# Bank_0_Bank_14.net
KiCad netlist of a schematic drawn in Altium Designer
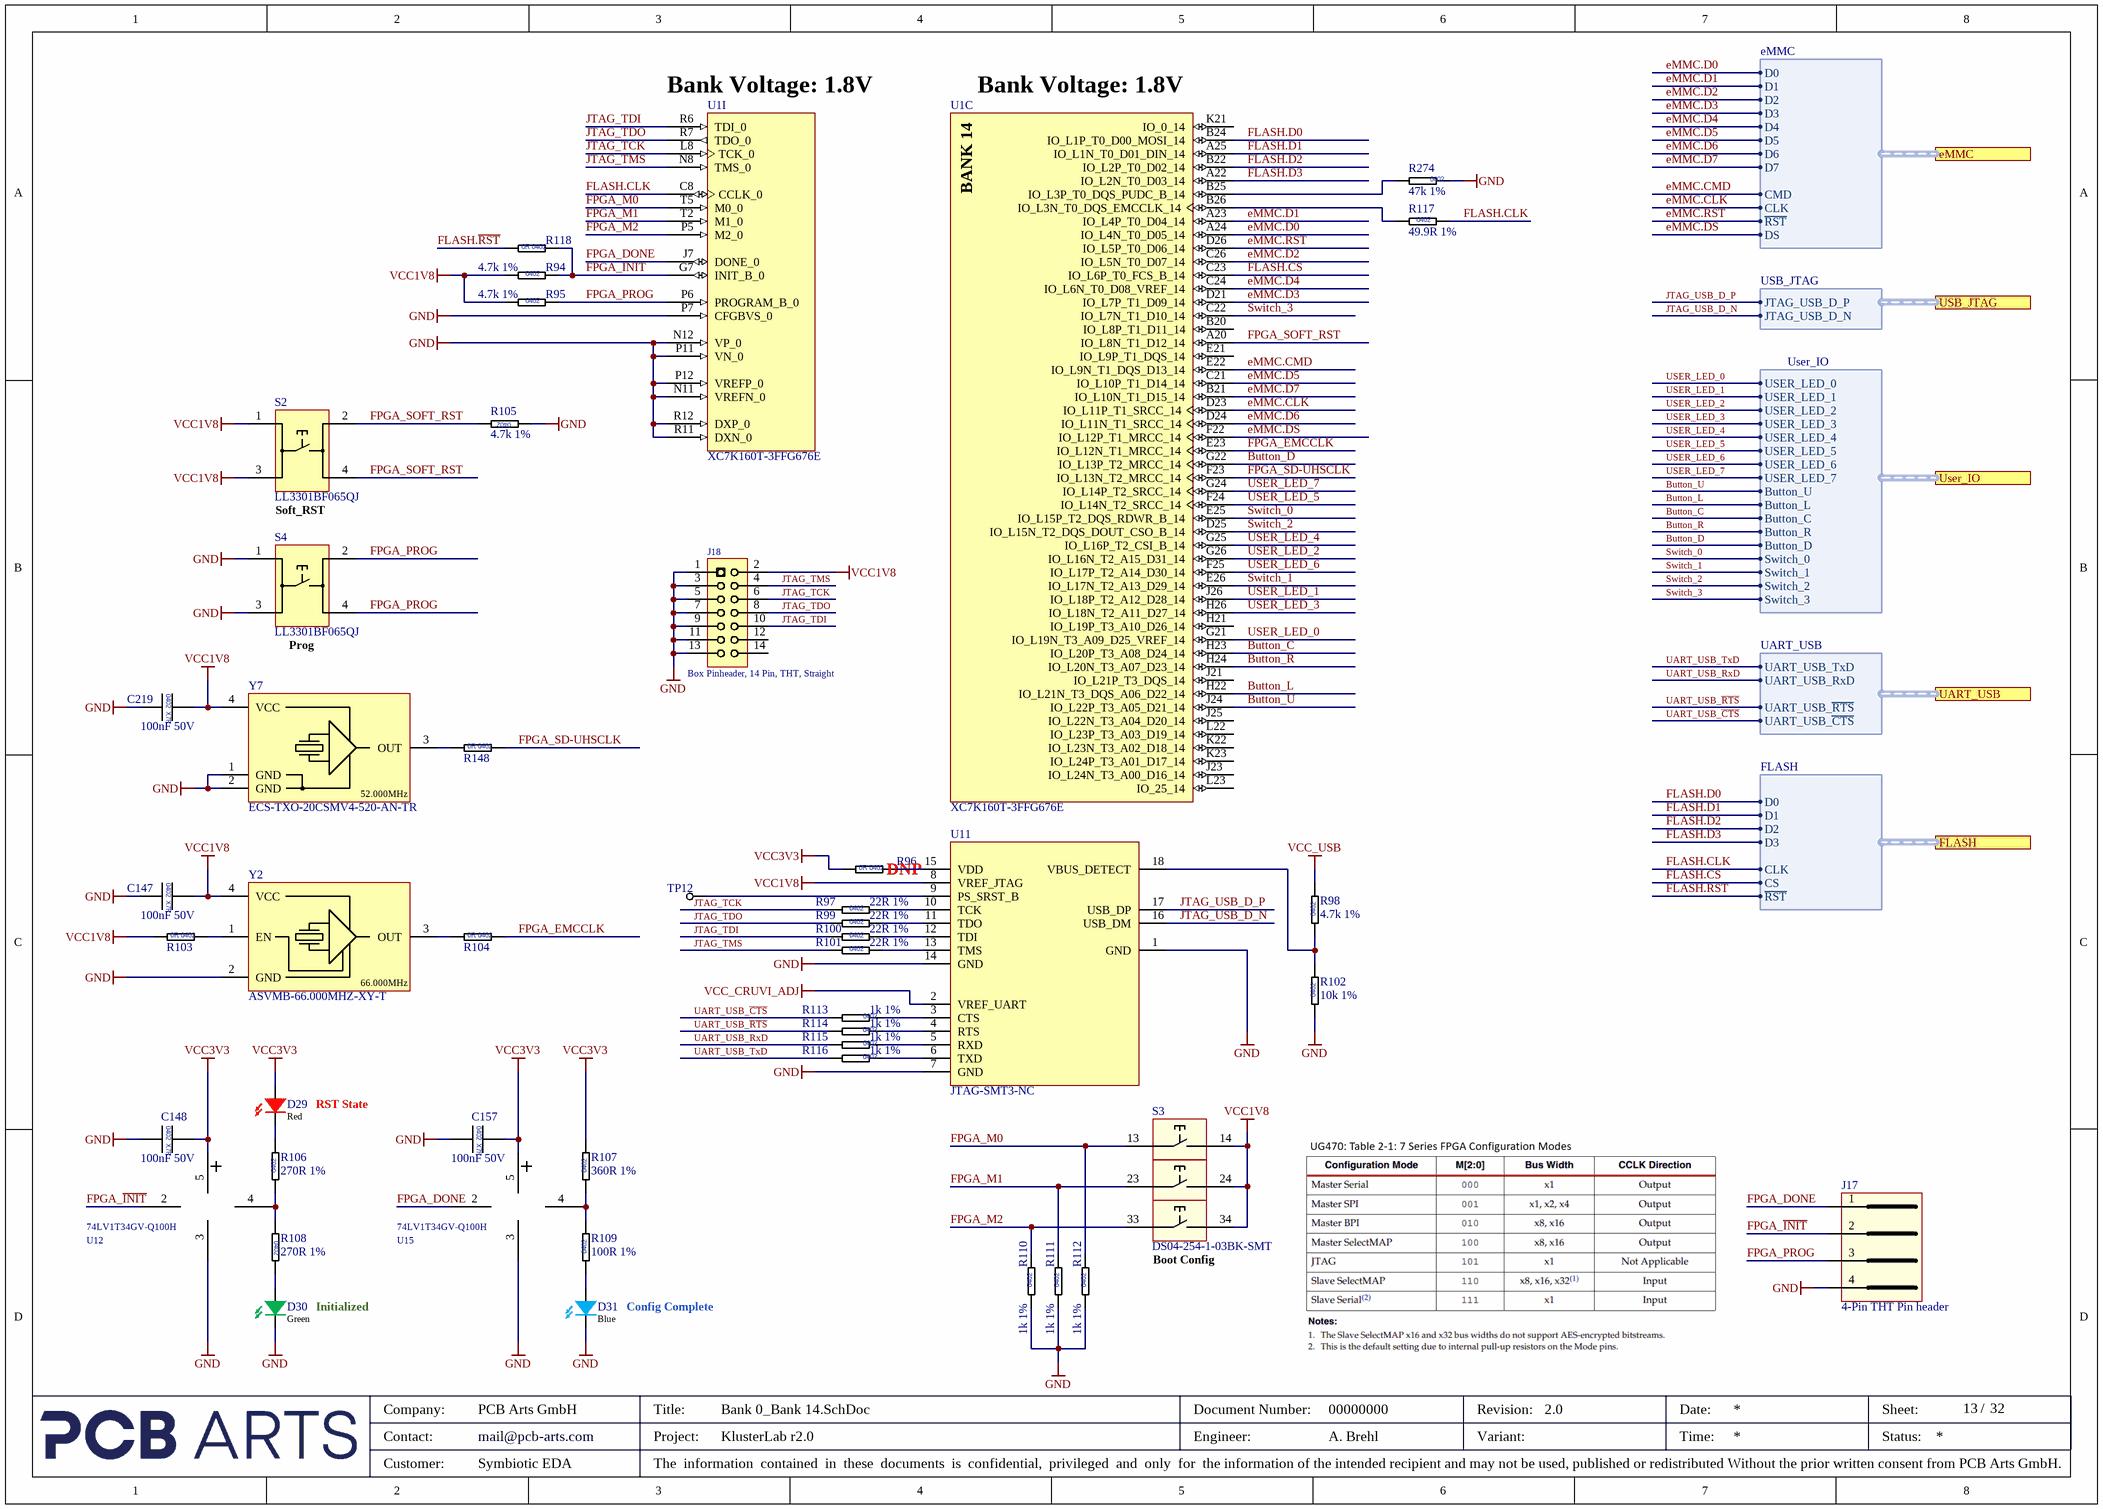
[diagram p0: Bank 0_Bank 14.SchDoc]

(export (version "E")
  (design (tool "Eeschema 10.0.6"))
  (components
    (comp (ref "C147")
      (value "100nF 50V")
      (footprint "Cap:CAP_0402_L")
      (description "Multilayer Ceramic Capacitors MLCC - SMD/SMT 0402 50VDC")
      (libsource (lib "Cap") (part "CAP_0402_100nF_50V"))
    )
    (comp (ref "C148")
      (value "100nF 50V")
      (footprint "Cap:CAP_0402_L")
      (description "Multilayer Ceramic Capacitors MLCC - SMD/SMT 0402 50VDC")
      (libsource (lib "Cap") (part "CAP_0402_100nF_50V"))
    )
    (comp (ref "C157")
      (value "100nF 50V")
      (footprint "Cap:CAP_0402_L")
      (description "Multilayer Ceramic Capacitors MLCC - SMD/SMT 0402 50VDC")
      (libsource (lib "Cap") (part "CAP_0402_100nF_50V"))
    )
    (comp (ref "C219")
      (value "100nF 50V")
      (footprint "Cap:CAP_0402_L")
      (description "Multilayer Ceramic Capacitors MLCC - SMD/SMT 0402 50VDC")
      (libsource (lib "Cap") (part "CAP_0402_100nF_50V"))
    )
    (comp (ref "D29")
      (value "LTST-S270KRKT")
      (footprint "Active:LED-0603 Sideview")
      (description "RED  0603 Light Emitting Diode")
      (fields (field (name "COLOR") "Red"))
      (libsource (lib "Active") (part "LED 0603 Red Sideview"))
    )
    (comp (ref "D30")
      (value "LTST-S270KGKT")
      (footprint "Active:LED-0603 Sideview")
      (description "GREEN  0603 Light Emitting Diode")
      (fields (field (name "COLOR") "Green"))
      (libsource (lib "Active") (part "LED 0603 Green Sideview"))
    )
    (comp (ref "D31")
      (value "LTST-S270TBKT")
      (footprint "Active:LED-0603 Sideview")
      (description "BLUE  0603 Light Emitting Diode")
      (fields (field (name "COLOR") "Blue"))
      (libsource (lib "Active") (part "LED 0603 Blue Sideview"))
    )
    (comp (ref "J17")
      (value "4-Pin THT Pin header")
      (footprint "Conn:61300411121")
      (description "WR-PHD 2.54mm 4Pin THT Header")
      (libsource (lib "Conn") (part "61300411121_WR-PHD 2.54mm 4Pin THT Header"))
    )
    (comp (ref "J18")
      (value "Box Pinheader, 14 Pin, THT, Straight")
      (footprint "Conn:87832-1420")
      (description "Box Pin header THT 2.00mm 14Pol Straight")
      (libsource (lib "Conn") (part "87832-1420_Box Pin header THT 2.00mm Box 14Pol Straight"))
    )
    (comp (ref "R94")
      (value "4.7k 1%")
      (footprint "Res:RES_0402_L")
      (description "Thick Film Resistors - SMD 4.7kOhm 1%")
      (libsource (lib "Res") (part "RES_0402_4.7k_1%"))
    )
    (comp (ref "R95")
      (value "4.7k 1%")
      (footprint "Res:RES_0402_L")
      (description "Thick Film Resistors - SMD 4.7kOhm 1%")
      (libsource (lib "Res") (part "RES_0402_4.7k_1%"))
    )
    (comp (ref "R96")
      (value "0R Jumper")
      (footprint "Res:RES_0402_L")
      (description "Thick Film Resistors - SMD 0Ohm")
      (libsource (lib "Res") (part "RES_0402_0R Jumper"))
    )
    (comp (ref "R97")
      (value "22R 1%")
      (footprint "Res:RES_0402_L")
      (description "Thick Film Resistors - SMD 22Ohm 1%")
      (libsource (lib "Res") (part "RES_0402_22R_1%"))
    )
    (comp (ref "R98")
      (value "4.7k 1%")
      (footprint "Res:RES_0402_L")
      (description "Thick Film Resistors - SMD 4.7kOhm 1%")
      (libsource (lib "Res") (part "RES_0402_4.7k_1%"))
    )
    (comp (ref "R99")
      (value "22R 1%")
      (footprint "Res:RES_0402_L")
      (description "Thick Film Resistors - SMD 22Ohm 1%")
      (libsource (lib "Res") (part "RES_0402_22R_1%"))
    )
    (comp (ref "R100")
      (value "22R 1%")
      (footprint "Res:RES_0402_L")
      (description "Thick Film Resistors - SMD 22Ohm 1%")
      (libsource (lib "Res") (part "RES_0402_22R_1%"))
    )
    (comp (ref "R101")
      (value "22R 1%")
      (footprint "Res:RES_0402_L")
      (description "Thick Film Resistors - SMD 22Ohm 1%")
      (libsource (lib "Res") (part "RES_0402_22R_1%"))
    )
    (comp (ref "R102")
      (value "10k 1%")
      (footprint "Res:RES_0402_L")
      (description "Thick Film Resistors - SMD 10kOhm 1%")
      (libsource (lib "Res") (part "RES_0402_10k_1%"))
    )
    (comp (ref "R103")
      (value "0R Jumper")
      (footprint "Res:RES_0402_L")
      (description "Thick Film Resistors - SMD 0Ohm")
      (libsource (lib "Res") (part "RES_0402_0R Jumper"))
    )
    (comp (ref "R104")
      (value "0R Jumper")
      (footprint "Res:RES_0402_L")
      (description "Thick Film Resistors - SMD 0Ohm")
      (libsource (lib "Res") (part "RES_0402_0R Jumper"))
    )
    (comp (ref "R105")
      (value "4.7k 1%")
      (footprint "Res:RES_0402_L")
      (description "Thick Film Resistors - SMD 4.7kOhm 1%")
      (libsource (lib "Res") (part "RES_0402_4.7k_1%"))
    )
    (comp (ref "R106")
      (value "270R 1%")
      (footprint "Res:RES_0402_L")
      (description "Thick Film Resistors - SMD 270Ohm 1%")
      (libsource (lib "Res") (part "RES_0402_270R 1%"))
    )
    (comp (ref "R107")
      (value "360R 1%")
      (footprint "Res:RES_0402_L")
      (description "Thick Film Resistors - SMD 360Ohm 1%")
      (libsource (lib "Res") (part "RES_0402_360R_1%"))
    )
    (comp (ref "R108")
      (value "270R 1%")
      (footprint "Res:RES_0402_L")
      (description "Thick Film Resistors - SMD 270Ohm 1%")
      (libsource (lib "Res") (part "RES_0402_270R 1%"))
    )
    (comp (ref "R109")
      (value "100R 1%")
      (footprint "Res:RES_0402_L")
      (description "Thick Film Resistors - SMD 100Ohm 1%")
      (libsource (lib "Res") (part "RES_0402_100R_1%"))
    )
    (comp (ref "R110")
      (value "1k 1%")
      (footprint "Res:RES_0402_L")
      (description "Thick Film Resistors - SMD 1kOhm 1%")
      (libsource (lib "Res") (part "RES_0402_1k_1%"))
    )
    (comp (ref "R111")
      (value "1k 1%")
      (footprint "Res:RES_0402_L")
      (description "Thick Film Resistors - SMD 1kOhm 1%")
      (libsource (lib "Res") (part "RES_0402_1k_1%"))
    )
    (comp (ref "R112")
      (value "1k 1%")
      (footprint "Res:RES_0402_L")
      (description "Thick Film Resistors - SMD 1kOhm 1%")
      (libsource (lib "Res") (part "RES_0402_1k_1%"))
    )
    (comp (ref "R113")
      (value "1k 1%")
      (footprint "Res:RES_0402_L")
      (description "Thick Film Resistors - SMD 1kOhm 1%")
      (libsource (lib "Res") (part "RES_0402_1k_1%"))
    )
    (comp (ref "R114")
      (value "1k 1%")
      (footprint "Res:RES_0402_L")
      (description "Thick Film Resistors - SMD 1kOhm 1%")
      (libsource (lib "Res") (part "RES_0402_1k_1%"))
    )
    (comp (ref "R115")
      (value "1k 1%")
      (footprint "Res:RES_0402_L")
      (description "Thick Film Resistors - SMD 1kOhm 1%")
      (libsource (lib "Res") (part "RES_0402_1k_1%"))
    )
    (comp (ref "R116")
      (value "1k 1%")
      (footprint "Res:RES_0402_L")
      (description "Thick Film Resistors - SMD 1kOhm 1%")
      (libsource (lib "Res") (part "RES_0402_1k_1%"))
    )
    (comp (ref "R117")
      (value "49.9R 1%")
      (footprint "Res:RES_0402_L")
      (description "Thick Film Resistors - SMD 49.9Ohm 1%")
      (libsource (lib "Res") (part "RES_0402_49.9R_1%"))
    )
    (comp (ref "R118")
      (value "0R Jumper")
      (footprint "Res:RES_0402_L")
      (description "Thick Film Resistors - SMD 0Ohm")
      (libsource (lib "Res") (part "RES_0402_0R Jumper"))
    )
    (comp (ref "R148")
      (value "0R Jumper")
      (footprint "Res:RES_0402_L")
      (description "Thick Film Resistors - SMD 0Ohm")
      (libsource (lib "Res") (part "RES_0402_0R Jumper"))
    )
    (comp (ref "R274")
      (value "47k 1%")
      (footprint "Res:RES_0402_L")
      (description "Thick Film Resistors - SMD 47kOhm 1%")
      (libsource (lib "Res") (part "RES_0402_47k_1%"))
    )
    (comp (ref "S2")
      (value "LL3301BF065QJ")
      (footprint "Electro_Mech:LL3301BF065QJ")
      (description "SPST Top Actuated  Button, 65gf, SMD h: 9.8mm")
      (libsource (lib "Electro_Mech") (part "LL3301BF065QJ_SPST Top Actuated  Button, 65gf, SMD h{colon} 9.8mm"))
    )
    (comp (ref "S3")
      (value "DS04-254-1-03BK-SMT")
      (footprint "Electro_Mech:CUI DS04-254-SMT Series, 3 Pole")
      (description "SMD DIP Switch, 3 Pos, Slide actuator")
      (libsource (lib "Electro_Mech") (part "DS04-254-1-03BK-SMT"))
    )
    (comp (ref "S4")
      (value "LL3301BF065QJ")
      (footprint "Electro_Mech:LL3301BF065QJ")
      (description "SPST Top Actuated  Button, 65gf, SMD h: 9.8mm")
      (libsource (lib "Electro_Mech") (part "LL3301BF065QJ_SPST Top Actuated  Button, 65gf, SMD h{colon} 9.8mm"))
    )
    (comp (ref "TP12")
      (value "Testpoint")
      (footprint "Electro_mech:Testpoint 0.8mm")
      (description "Testpoint 0.8mm")
      (libsource (lib "Electro_Mech") (part "Testpoint 0.8mm"))
    )
    (comp (ref "U1")
      (value "XC7K160T-3FFG676E")
      (footprint "Digital:BGA100P2700X2700X317-676N")
      (description "Kintex-7 FPGA, 400 User I/Os, 8 GTX, 676-Ball BGA, Speed Grade 3, Extended Grade, Pb-Free")
      (libsource (lib "Digital") (part "XC7K160T-3FFG676E_Kintex-7 FPGA, 400 User I/Os, 8 GTX, FFG676"))
    )
    (comp (ref "U11")
      (value "JTAG-SMT3-NC")
      (footprint "Conn_Modules:JTAG-SMT3-NC")
      (description "Surface-mount JTAG Programming + UART Module")
      (libsource (lib "Conn_Modules") (part "JTAG-SMT3-NC_Surface-mount JTAG Programming + UART Module"))
    )
    (comp (ref "U12")
      (value "74LV1T34GV-Q100H")
      (footprint "Digital:SOT95P275X110-5N")
      (description "Single supply translating buffer")
      (libsource (lib "Digital") (part "74LV1T34GV-Q100H_Single supply translating buffe"))
    )
    (comp (ref "U15")
      (value "74LV1T34GV-Q100H")
      (footprint "Digital:SOT95P275X110-5N")
      (description "Single supply translating buffer")
      (libsource (lib "Digital") (part "74LV1T34GV-Q100H_Single supply translating buffe"))
    )
    (comp (ref "Y2")
      (value "ASVMB-66.000MHZ-XY-T")
      (footprint "Timer:ASVMB Series")
      (description "Clock-Memsoszillator 66.000MHz 1.8V 10ppm -40C +105C")
      (libsource (lib "Timer") (part "ASVMB-66.000MHZ-XY-T_Clock-Memsoszillator 66.000MHz 1.8V 10ppm -40C +105C"))
    )
    (comp (ref "Y7")
      (value "ECS-TXO-20CSMV4-520-AN-TR")
      (footprint "Timer:ECS-TXO-20CSMV4_2X1.6X0.8")
      (description "Clock-Standardoszillatoren 52.000MHz 1.7V 3.6V 0.5ppm -40C +85C")
      (libsource (lib "Timer") (part "ECS-TXO-20CSMV4-520-AN-TR_52.000MHz Clock Oscillator, 1V7-3V6"))
    )
  )
  (nets
    (net (code "6") (name "/Button_C") (class "Default")
      (node (ref "U1") (pin "H23") (pinfunction "IO_L20P_T3_A08_D24_14_H23") (pintype "bidirectional"))
    )
    (net (code "7") (name "/Button_D") (class "Default")
      (node (ref "U1") (pin "G22") (pinfunction "IO_L13P_T2_MRCC_14_G22") (pintype "bidirectional"))
    )
    (net (code "8") (name "/Button_L") (class "Default")
      (node (ref "U1") (pin "H22") (pinfunction "IO_L21N_T3_DQS_A06_D22_14_H22") (pintype "bidirectional"))
    )
    (net (code "9") (name "/Button_R") (class "Default")
      (node (ref "U1") (pin "H24") (pinfunction "IO_L20N_T3_A07_D23_14_H24") (pintype "bidirectional"))
    )
    (net (code "10") (name "/Button_U") (class "Default")
      (node (ref "U1") (pin "J24") (pinfunction "IO_L22P_T3_A05_D21_14_J24") (pintype "bidirectional"))
    )
    (net (code "11") (name "/FLASH.CLK") (class "Default")
      (node (ref "R117") (pin "2") (pinfunction "2_2") (pintype "passive"))
      (node (ref "U1") (pin "C8") (pinfunction "CCLK_0_C8") (pintype "bidirectional"))
    )
    (net (code "12") (name "/FLASH.D0") (class "Default")
      (node (ref "U1") (pin "B24") (pinfunction "IO_L1P_T0_D00_MOSI_14_B24") (pintype "bidirectional"))
    )
    (net (code "13") (name "/FLASH.D1") (class "Default")
      (node (ref "U1") (pin "A25") (pinfunction "IO_L1N_T0_D01_DIN_14_A25") (pintype "bidirectional"))
    )
    (net (code "14") (name "/FLASH.D2") (class "Default")
      (node (ref "U1") (pin "B22") (pinfunction "IO_L2P_T0_D02_14_B22") (pintype "bidirectional"))
    )
    (net (code "15") (name "/FLASH.D3") (class "Default")
      (node (ref "U1") (pin "A22") (pinfunction "IO_L2N_T0_D03_14_A22") (pintype "bidirectional"))
    )
    (net (code "16") (name "/FLASH.~{CS}") (class "Default")
      (node (ref "U1") (pin "C23") (pinfunction "IO_L6P_T0_FCS_B_14_C23") (pintype "bidirectional"))
    )
    (net (code "17") (name "/FLASH.~{RST}") (class "Default")
      (node (ref "R118") (pin "1") (pinfunction "1_1") (pintype "passive"))
    )
    (net (code "18") (name "/FPGA_DONE") (class "Default")
      (node (ref "J17") (pin "1") (pinfunction "1_1") (pintype "passive"))
      (node (ref "U1") (pin "J7") (pinfunction "DONE_0_J7") (pintype "bidirectional"))
      (node (ref "U15") (pin "2") (pinfunction "A_2") (pintype "passive"))
    )
    (net (code "19") (name "/FPGA_EMCCLK") (class "Default")
      (node (ref "R104") (pin "2") (pinfunction "2_2") (pintype "passive"))
      (node (ref "U1") (pin "E23") (pinfunction "IO_L12N_T1_MRCC_14_E23") (pintype "bidirectional"))
    )
    (net (code "20") (name "/FPGA_M0") (class "Default")
      (node (ref "R112") (pin "2") (pinfunction "2_2") (pintype "passive"))
      (node (ref "S3") (pin "13") (pinfunction "13_13") (pintype "passive"))
      (node (ref "U1") (pin "T5") (pinfunction "M0_0_T5") (pintype "input"))
    )
    (net (code "21") (name "/FPGA_M1") (class "Default")
      (node (ref "R111") (pin "2") (pinfunction "2_2") (pintype "passive"))
      (node (ref "S3") (pin "23") (pinfunction "23_23") (pintype "passive"))
      (node (ref "U1") (pin "T2") (pinfunction "M1_0_T2") (pintype "input"))
    )
    (net (code "22") (name "/FPGA_M2") (class "Default")
      (node (ref "R110") (pin "2") (pinfunction "2_2") (pintype "passive"))
      (node (ref "S3") (pin "33") (pinfunction "33_33") (pintype "passive"))
      (node (ref "U1") (pin "P5") (pinfunction "M2_0_P5") (pintype "input"))
    )
    (net (code "23") (name "/FPGA_PROG") (class "Default")
      (node (ref "J17") (pin "3") (pinfunction "3_3") (pintype "passive"))
      (node (ref "R95") (pin "2") (pinfunction "2_2") (pintype "passive"))
      (node (ref "S4") (pin "2") (pinfunction "2_2") (pintype "passive"))
      (node (ref "S4") (pin "4") (pinfunction "4_4") (pintype "passive"))
      (node (ref "U1") (pin "P6") (pinfunction "PROGRAM_B_0_P6") (pintype "input"))
    )
    (net (code "24") (name "/FPGA_SD-UHSCLK") (class "Default")
      (node (ref "R148") (pin "2") (pinfunction "2_2") (pintype "passive"))
      (node (ref "U1") (pin "F23") (pinfunction "IO_L13N_T2_MRCC_14_F23") (pintype "bidirectional"))
    )
    (net (code "25") (name "/FPGA_SOFT_RST") (class "Default")
      (node (ref "R105") (pin "2") (pinfunction "2_2") (pintype "passive"))
      (node (ref "S2") (pin "2") (pinfunction "2_2") (pintype "passive"))
      (node (ref "S2") (pin "4") (pinfunction "4_4") (pintype "passive"))
      (node (ref "U1") (pin "A20") (pinfunction "IO_L8N_T1_D12_14_A20") (pintype "bidirectional"))
    )
    (net (code "26") (name "/FPGA_~{INIT}") (class "Default")
      (node (ref "J17") (pin "2") (pinfunction "2_2") (pintype "passive"))
      (node (ref "R118") (pin "2") (pinfunction "2_2") (pintype "passive"))
      (node (ref "R94") (pin "2") (pinfunction "2_2") (pintype "passive"))
      (node (ref "U1") (pin "G7") (pinfunction "INIT_B_0_G7") (pintype "bidirectional"))
      (node (ref "U12") (pin "2") (pinfunction "A_2") (pintype "passive"))
    )
    (net (code "27") (name "/JTAG_TCK") (class "Default")
      (node (ref "J18") (pin "6") (pinfunction "6_6") (pintype "passive"))
      (node (ref "R97") (pin "1") (pinfunction "1_1") (pintype "passive"))
      (node (ref "U1") (pin "L8") (pinfunction "TCK_0_L8") (pintype "input"))
    )
    (net (code "28") (name "/JTAG_TDI") (class "Default")
      (node (ref "J18") (pin "10") (pinfunction "10_10") (pintype "passive"))
      (node (ref "R100") (pin "1") (pinfunction "1_1") (pintype "passive"))
      (node (ref "U1") (pin "R6") (pinfunction "TDI_0_R6") (pintype "input"))
    )
    (net (code "29") (name "/JTAG_TDO") (class "Default")
      (node (ref "J18") (pin "8") (pinfunction "8_8") (pintype "passive"))
      (node (ref "R99") (pin "1") (pinfunction "1_1") (pintype "passive"))
      (node (ref "U1") (pin "R7") (pinfunction "TDO_0_R7") (pintype "output"))
    )
    (net (code "30") (name "/JTAG_TMS") (class "Default")
      (node (ref "J18") (pin "4") (pinfunction "4_4") (pintype "passive"))
      (node (ref "R101") (pin "1") (pinfunction "1_1") (pintype "passive"))
      (node (ref "U1") (pin "N8") (pinfunction "TMS_0_N8") (pintype "input"))
    )
    (net (code "31") (name "/JTAG_USB_D_N") (class "Default")
      (node (ref "U11") (pin "16") (pinfunction "USB_DM_16") (pintype "passive"))
    )
    (net (code "32") (name "/JTAG_USB_D_P") (class "Default")
      (node (ref "U11") (pin "17") (pinfunction "USB_DP_17") (pintype "passive"))
    )
    (net (code "33") (name "/Switch_0") (class "Default")
      (node (ref "U1") (pin "E25") (pinfunction "IO_L15P_T2_DQS_RDWR_B_14_E25") (pintype "bidirectional"))
    )
    (net (code "34") (name "/Switch_1") (class "Default")
      (node (ref "U1") (pin "E26") (pinfunction "IO_L17N_T2_A13_D29_14_E26") (pintype "bidirectional"))
    )
    (net (code "35") (name "/Switch_2") (class "Default")
      (node (ref "U1") (pin "D25") (pinfunction "IO_L15N_T2_DQS_DOUT_CSO_B_14_D25") (pintype "bidirectional"))
    )
    (net (code "36") (name "/Switch_3") (class "Default")
      (node (ref "U1") (pin "C22") (pinfunction "IO_L7N_T1_D10_14_C22") (pintype "bidirectional"))
    )
    (net (code "37") (name "/UART_USB_RxD") (class "Default")
      (node (ref "R115") (pin "2") (pinfunction "2_2") (pintype "passive"))
    )
    (net (code "38") (name "/UART_USB_TxD") (class "Default")
      (node (ref "R116") (pin "2") (pinfunction "2_2") (pintype "passive"))
    )
    (net (code "39") (name "/UART_USB_~{CTS}") (class "Default")
      (node (ref "R113") (pin "2") (pinfunction "2_2") (pintype "passive"))
    )
    (net (code "40") (name "/UART_USB_~{RTS}") (class "Default")
      (node (ref "R114") (pin "2") (pinfunction "2_2") (pintype "passive"))
    )
    (net (code "41") (name "/USER_LED_0") (class "Default")
      (node (ref "U1") (pin "G21") (pinfunction "IO_L19N_T3_A09_D25_VREF_14_G21") (pintype "bidirectional"))
    )
    (net (code "42") (name "/USER_LED_1") (class "Default")
      (node (ref "U1") (pin "J26") (pinfunction "IO_L18P_T2_A12_D28_14_J26") (pintype "bidirectional"))
    )
    (net (code "43") (name "/USER_LED_2") (class "Default")
      (node (ref "U1") (pin "G26") (pinfunction "IO_L16N_T2_A15_D31_14_G26") (pintype "bidirectional"))
    )
    (net (code "44") (name "/USER_LED_3") (class "Default")
      (node (ref "U1") (pin "H26") (pinfunction "IO_L18N_T2_A11_D27_14_H26") (pintype "bidirectional"))
    )
    (net (code "45") (name "/USER_LED_4") (class "Default")
      (node (ref "U1") (pin "G25") (pinfunction "IO_L16P_T2_CSI_B_14_G25") (pintype "bidirectional"))
    )
    (net (code "46") (name "/USER_LED_5") (class "Default")
      (node (ref "U1") (pin "F24") (pinfunction "IO_L14N_T2_SRCC_14_F24") (pintype "bidirectional"))
    )
    (net (code "47") (name "/USER_LED_6") (class "Default")
      (node (ref "U1") (pin "F25") (pinfunction "IO_L17P_T2_A14_D30_14_F25") (pintype "bidirectional"))
    )
    (net (code "48") (name "/USER_LED_7") (class "Default")
      (node (ref "U1") (pin "G24") (pinfunction "IO_L14P_T2_SRCC_14_G24") (pintype "bidirectional"))
    )
    (net (code "49") (name "/eMMC.CLK") (class "Default")
      (node (ref "U1") (pin "D23") (pinfunction "IO_L11P_T1_SRCC_14_D23") (pintype "bidirectional"))
    )
    (net (code "50") (name "/eMMC.CMD") (class "Default")
      (node (ref "U1") (pin "E22") (pinfunction "IO_L9N_T1_DQS_D13_14_E22") (pintype "bidirectional"))
    )
    (net (code "51") (name "/eMMC.D0") (class "Default")
      (node (ref "U1") (pin "A24") (pinfunction "IO_L4N_T0_D05_14_A24") (pintype "bidirectional"))
    )
    (net (code "52") (name "/eMMC.D1") (class "Default")
      (node (ref "U1") (pin "A23") (pinfunction "IO_L4P_T0_D04_14_A23") (pintype "bidirectional"))
    )
    (net (code "53") (name "/eMMC.D2") (class "Default")
      (node (ref "U1") (pin "C26") (pinfunction "IO_L5N_T0_D07_14_C26") (pintype "bidirectional"))
    )
    (net (code "54") (name "/eMMC.D3") (class "Default")
      (node (ref "U1") (pin "D21") (pinfunction "IO_L7P_T1_D09_14_D21") (pintype "bidirectional"))
    )
    (net (code "55") (name "/eMMC.D4") (class "Default")
      (node (ref "U1") (pin "C24") (pinfunction "IO_L6N_T0_D08_VREF_14_C24") (pintype "bidirectional"))
    )
    (net (code "56") (name "/eMMC.D5") (class "Default")
      (node (ref "U1") (pin "C21") (pinfunction "IO_L10P_T1_D14_14_C21") (pintype "bidirectional"))
    )
    (net (code "57") (name "/eMMC.D6") (class "Default")
      (node (ref "U1") (pin "D24") (pinfunction "IO_L11N_T1_SRCC_14_D24") (pintype "bidirectional"))
    )
    (net (code "58") (name "/eMMC.D7") (class "Default")
      (node (ref "U1") (pin "B21") (pinfunction "IO_L10N_T1_D15_14_B21") (pintype "bidirectional"))
    )
    (net (code "59") (name "/eMMC.DS") (class "Default")
      (node (ref "U1") (pin "F22") (pinfunction "IO_L12P_T1_MRCC_14_F22") (pintype "bidirectional"))
    )
    (net (code "60") (name "/eMMC.~{RST}") (class "Default")
      (node (ref "U1") (pin "D26") (pinfunction "IO_L5P_T0_D06_14_D26") (pintype "bidirectional"))
    )
    (net (code "66") (name "GND") (class "Default")
      (node (ref "C147") (pin "2") (pinfunction "2_2") (pintype "passive"))
      (node (ref "C148") (pin "2") (pinfunction "2_2") (pintype "passive"))
      (node (ref "C157") (pin "2") (pinfunction "2_2") (pintype "passive"))
      (node (ref "C219") (pin "2") (pinfunction "2_2") (pintype "passive"))
      (node (ref "D30") (pin "1") (pinfunction "1_1") (pintype "passive"))
      (node (ref "D31") (pin "1") (pinfunction "1_1") (pintype "passive"))
      (node (ref "J17") (pin "4") (pinfunction "4_4") (pintype "passive"))
      (node (ref "J18") (pin "1") (pinfunction "1_1") (pintype "passive"))
      (node (ref "J18") (pin "11") (pinfunction "11_11") (pintype "passive"))
      (node (ref "J18") (pin "13") (pinfunction "13_13") (pintype "passive"))
      (node (ref "J18") (pin "3") (pinfunction "3_3") (pintype "passive"))
      (node (ref "J18") (pin "5") (pinfunction "5_5") (pintype "passive"))
      (node (ref "J18") (pin "7") (pinfunction "7_7") (pintype "passive"))
      (node (ref "J18") (pin "9") (pinfunction "9_9") (pintype "passive"))
      (node (ref "R102") (pin "1") (pinfunction "1_1") (pintype "passive"))
      (node (ref "R105") (pin "1") (pinfunction "1_1") (pintype "passive"))
      (node (ref "R110") (pin "1") (pinfunction "1_1") (pintype "passive"))
      (node (ref "R111") (pin "1") (pinfunction "1_1") (pintype "passive"))
      (node (ref "R112") (pin "1") (pinfunction "1_1") (pintype "passive"))
      (node (ref "R274") (pin "1") (pinfunction "1_1") (pintype "passive"))
      (node (ref "S4") (pin "1") (pinfunction "1_1") (pintype "passive"))
      (node (ref "S4") (pin "3") (pinfunction "3_3") (pintype "passive"))
      (node (ref "U1") (pin "N11") (pinfunction "VREFN_0_N11") (pintype "input"))
      (node (ref "U1") (pin "N12") (pinfunction "VP_0_N12") (pintype "input"))
      (node (ref "U1") (pin "P11") (pinfunction "VN_0_P11") (pintype "input"))
      (node (ref "U1") (pin "P12") (pinfunction "VREFP_0_P12") (pintype "input"))
      (node (ref "U1") (pin "P7") (pinfunction "CFGBVS_0_P7") (pintype "input"))
      (node (ref "U1") (pin "R11") (pinfunction "DXN_0_R11") (pintype "input"))
      (node (ref "U1") (pin "R12") (pinfunction "DXP_0_R12") (pintype "input"))
      (node (ref "U11") (pin "1") (pinfunction "GND_1") (pintype "passive"))
      (node (ref "U11") (pin "14") (pinfunction "GND_14") (pintype "passive"))
      (node (ref "U11") (pin "7") (pinfunction "GND_7") (pintype "passive"))
      (node (ref "U12") (pin "3") (pinfunction "GND_3") (pintype "passive"))
      (node (ref "U15") (pin "3") (pinfunction "GND_3") (pintype "passive"))
      (node (ref "Y2") (pin "2") (pinfunction "GND_2") (pintype "passive"))
      (node (ref "Y7") (pin "1") (pinfunction "GND_1") (pintype "passive"))
      (node (ref "Y7") (pin "2") (pinfunction "GND_2") (pintype "passive"))
    )
    (net (code "67") (name "Net-(D29-Pad1)") (class "Default")
      (node (ref "D29") (pin "1") (pinfunction "1_1") (pintype "passive"))
      (node (ref "R106") (pin "2") (pinfunction "2_2") (pintype "passive"))
    )
    (net (code "68") (name "Net-(D30-Pad2)") (class "Default")
      (node (ref "D30") (pin "2") (pinfunction "2_2") (pintype "passive"))
      (node (ref "R108") (pin "2") (pinfunction "2_2") (pintype "passive"))
    )
    (net (code "69") (name "Net-(D31-Pad2)") (class "Default")
      (node (ref "D31") (pin "2") (pinfunction "2_2") (pintype "passive"))
      (node (ref "R109") (pin "1") (pinfunction "1_1") (pintype "passive"))
    )
    (net (code "70") (name "Net-(TP12-GND)") (class "Default")
      (node (ref "TP12") (pin "1") (pinfunction "GND_1") (pintype "passive"))
      (node (ref "U11") (pin "9") (pinfunction "PS_SRST_B_9") (pintype "passive"))
    )
    (net (code "71") (name "Net-(U1C-IO_L3N_T0_DQS_EMCCLK_14)") (class "Default")
      (node (ref "R117") (pin "1") (pinfunction "1_1") (pintype "passive"))
      (node (ref "U1") (pin "B26") (pinfunction "IO_L3N_T0_DQS_EMCCLK_14_B26") (pintype "bidirectional"))
    )
    (net (code "72") (name "Net-(U1C-IO_L3P_T0_DQS_PUDC_B_14)") (class "Default")
      (node (ref "R274") (pin "2") (pinfunction "2_2") (pintype "passive"))
      (node (ref "U1") (pin "B25") (pinfunction "IO_L3P_T0_DQS_PUDC_B_14_B25") (pintype "bidirectional"))
    )
    (net (code "73") (name "Net-(U11-CTS)") (class "Default")
      (node (ref "R113") (pin "1") (pinfunction "1_1") (pintype "passive"))
      (node (ref "U11") (pin "3") (pinfunction "CTS_3") (pintype "passive"))
    )
    (net (code "74") (name "Net-(U11-RTS)") (class "Default")
      (node (ref "R114") (pin "1") (pinfunction "1_1") (pintype "passive"))
      (node (ref "U11") (pin "4") (pinfunction "RTS_4") (pintype "passive"))
    )
    (net (code "75") (name "Net-(U11-RXD)") (class "Default")
      (node (ref "R115") (pin "1") (pinfunction "1_1") (pintype "passive"))
      (node (ref "U11") (pin "5") (pinfunction "RXD_5") (pintype "passive"))
    )
    (net (code "76") (name "Net-(U11-TCK)") (class "Default")
      (node (ref "R97") (pin "2") (pinfunction "2_2") (pintype "passive"))
      (node (ref "U11") (pin "10") (pinfunction "TCK_10") (pintype "passive"))
    )
    (net (code "77") (name "Net-(U11-TDI)") (class "Default")
      (node (ref "R100") (pin "2") (pinfunction "2_2") (pintype "passive"))
      (node (ref "U11") (pin "12") (pinfunction "TDI_12") (pintype "passive"))
    )
    (net (code "78") (name "Net-(U11-TDO)") (class "Default")
      (node (ref "R99") (pin "2") (pinfunction "2_2") (pintype "passive"))
      (node (ref "U11") (pin "11") (pinfunction "TDO_11") (pintype "passive"))
    )
    (net (code "79") (name "Net-(U11-TMS)") (class "Default")
      (node (ref "R101") (pin "2") (pinfunction "2_2") (pintype "passive"))
      (node (ref "U11") (pin "13") (pinfunction "TMS_13") (pintype "passive"))
    )
    (net (code "80") (name "Net-(U11-TXD)") (class "Default")
      (node (ref "R116") (pin "1") (pinfunction "1_1") (pintype "passive"))
      (node (ref "U11") (pin "6") (pinfunction "TXD_6") (pintype "passive"))
    )
    (net (code "81") (name "Net-(U11-VBUS_DETECT)") (class "Default")
      (node (ref "R102") (pin "2") (pinfunction "2_2") (pintype "passive"))
      (node (ref "R98") (pin "1") (pinfunction "1_1") (pintype "passive"))
      (node (ref "U11") (pin "18") (pinfunction "VBUS_DETECT_18") (pintype "passive"))
    )
    (net (code "82") (name "Net-(U11-VDD)") (class "Default")
      (node (ref "R96") (pin "2") (pinfunction "2_2") (pintype "passive"))
      (node (ref "U11") (pin "15") (pinfunction "VDD_15") (pintype "passive"))
    )
    (net (code "83") (name "Net-(U12-Y)") (class "Default")
      (node (ref "R106") (pin "1") (pinfunction "1_1") (pintype "passive"))
      (node (ref "R108") (pin "1") (pinfunction "1_1") (pintype "passive"))
      (node (ref "U12") (pin "4") (pinfunction "Y_4") (pintype "passive"))
    )
    (net (code "84") (name "Net-(U15-Y)") (class "Default")
      (node (ref "R107") (pin "1") (pinfunction "1_1") (pintype "passive"))
      (node (ref "R109") (pin "2") (pinfunction "2_2") (pintype "passive"))
      (node (ref "U15") (pin "4") (pinfunction "Y_4") (pintype "passive"))
    )
    (net (code "85") (name "Net-(Y2-EN)") (class "Default")
      (node (ref "R103") (pin "2") (pinfunction "2_2") (pintype "passive"))
      (node (ref "Y2") (pin "1") (pinfunction "EN_1") (pintype "passive"))
    )
    (net (code "86") (name "Net-(Y2-OUT)") (class "Default")
      (node (ref "R104") (pin "1") (pinfunction "1_1") (pintype "passive"))
      (node (ref "Y2") (pin "3") (pinfunction "OUT_3") (pintype "passive"))
    )
    (net (code "87") (name "Net-(Y7-OUT)") (class "Default")
      (node (ref "R148") (pin "1") (pinfunction "1_1") (pintype "passive"))
      (node (ref "Y7") (pin "3") (pinfunction "OUT_3") (pintype "passive"))
    )
    (net (code "88") (name "VCC1V8") (class "Default")
      (node (ref "C147") (pin "1") (pinfunction "1_1") (pintype "passive"))
      (node (ref "C219") (pin "1") (pinfunction "1_1") (pintype "passive"))
      (node (ref "J18") (pin "2") (pinfunction "2_2") (pintype "passive"))
      (node (ref "R103") (pin "1") (pinfunction "1_1") (pintype "passive"))
      (node (ref "R94") (pin "1") (pinfunction "1_1") (pintype "passive"))
      (node (ref "R95") (pin "1") (pinfunction "1_1") (pintype "passive"))
      (node (ref "S2") (pin "1") (pinfunction "1_1") (pintype "passive"))
      (node (ref "S2") (pin "3") (pinfunction "3_3") (pintype "passive"))
      (node (ref "S3") (pin "14") (pinfunction "14_14") (pintype "passive"))
      (node (ref "S3") (pin "24") (pinfunction "24_24") (pintype "passive"))
      (node (ref "S3") (pin "34") (pinfunction "34_34") (pintype "passive"))
      (node (ref "U11") (pin "8") (pinfunction "VREF_JTAG_8") (pintype "passive"))
      (node (ref "Y2") (pin "4") (pinfunction "VCC_4") (pintype "passive"))
      (node (ref "Y7") (pin "4") (pinfunction "VCC_4") (pintype "passive"))
    )
    (net (code "89") (name "VCC3V3") (class "Default")
      (node (ref "C148") (pin "1") (pinfunction "1_1") (pintype "passive"))
      (node (ref "C157") (pin "1") (pinfunction "1_1") (pintype "passive"))
      (node (ref "D29") (pin "2") (pinfunction "2_2") (pintype "passive"))
      (node (ref "R107") (pin "2") (pinfunction "2_2") (pintype "passive"))
      (node (ref "R96") (pin "1") (pinfunction "1_1") (pintype "passive"))
      (node (ref "U12") (pin "5") (pinfunction "VCC_5") (pintype "passive"))
      (node (ref "U15") (pin "5") (pinfunction "VCC_5") (pintype "passive"))
    )
    (net (code "90") (name "VCC_CRUVI_ADJ") (class "Default")
      (node (ref "U11") (pin "2") (pinfunction "VREF_UART_2") (pintype "passive"))
    )
    (net (code "91") (name "VCC_USB") (class "Default")
      (node (ref "R98") (pin "2") (pinfunction "2_2") (pintype "passive"))
    )
    (net (code "92") (name "unconnected-(J18-Pad12)") (class "Default")
      (node (ref "J18") (pin "12") (pinfunction "12_12") (pintype "passive"))
    )
    (net (code "93") (name "unconnected-(J18-Pad14)") (class "Default")
      (node (ref "J18") (pin "14") (pinfunction "14_14") (pintype "passive"))
    )
    (net (code "94") (name "unconnected-(U1C-IO_0_14-PadK21)") (class "Default")
      (node (ref "U1") (pin "K21") (pinfunction "IO_0_14_K21") (pintype "bidirectional"))
    )
    (net (code "95") (name "unconnected-(U1C-IO_25_14-PadL23)") (class "Default")
      (node (ref "U1") (pin "L23") (pinfunction "IO_25_14_L23") (pintype "bidirectional"))
    )
    (net (code "96") (name "unconnected-(U1C-IO_L8P_T1_D11_14-PadB20)") (class "Default")
      (node (ref "U1") (pin "B20") (pinfunction "IO_L8P_T1_D11_14_B20") (pintype "bidirectional"))
    )
    (net (code "97") (name "unconnected-(U1C-IO_L9P_T1_DQS_14-PadE21)") (class "Default")
      (node (ref "U1") (pin "E21") (pinfunction "IO_L9P_T1_DQS_14_E21") (pintype "bidirectional"))
    )
    (net (code "98") (name "unconnected-(U1C-IO_L19P_T3_A10_D26_14-PadH21)") (class "Default")
      (node (ref "U1") (pin "H21") (pinfunction "IO_L19P_T3_A10_D26_14_H21") (pintype "bidirectional"))
    )
    (net (code "99") (name "unconnected-(U1C-IO_L21P_T3_DQS_14-PadJ21)") (class "Default")
      (node (ref "U1") (pin "J21") (pinfunction "IO_L21P_T3_DQS_14_J21") (pintype "bidirectional"))
    )
    (net (code "100") (name "unconnected-(U1C-IO_L22N_T3_A04_D20_14-PadJ25)") (class "Default")
      (node (ref "U1") (pin "J25") (pinfunction "IO_L22N_T3_A04_D20_14_J25") (pintype "bidirectional"))
    )
    (net (code "101") (name "unconnected-(U1C-IO_L23N_T3_A02_D18_14-PadK22)") (class "Default")
      (node (ref "U1") (pin "K22") (pinfunction "IO_L23N_T3_A02_D18_14_K22") (pintype "bidirectional"))
    )
    (net (code "102") (name "unconnected-(U1C-IO_L23P_T3_A03_D19_14-PadL22)") (class "Default")
      (node (ref "U1") (pin "L22") (pinfunction "IO_L23P_T3_A03_D19_14_L22") (pintype "bidirectional"))
    )
    (net (code "103") (name "unconnected-(U1C-IO_L24N_T3_A00_D16_14-PadJ23)") (class "Default")
      (node (ref "U1") (pin "J23") (pinfunction "IO_L24N_T3_A00_D16_14_J23") (pintype "bidirectional"))
    )
    (net (code "104") (name "unconnected-(U1C-IO_L24P_T3_A01_D17_14-PadK23)") (class "Default")
      (node (ref "U1") (pin "K23") (pinfunction "IO_L24P_T3_A01_D17_14_K23") (pintype "bidirectional"))
    )
  )
)
